# main.net
KiCad netlist of a schematic drawn in EAGLE
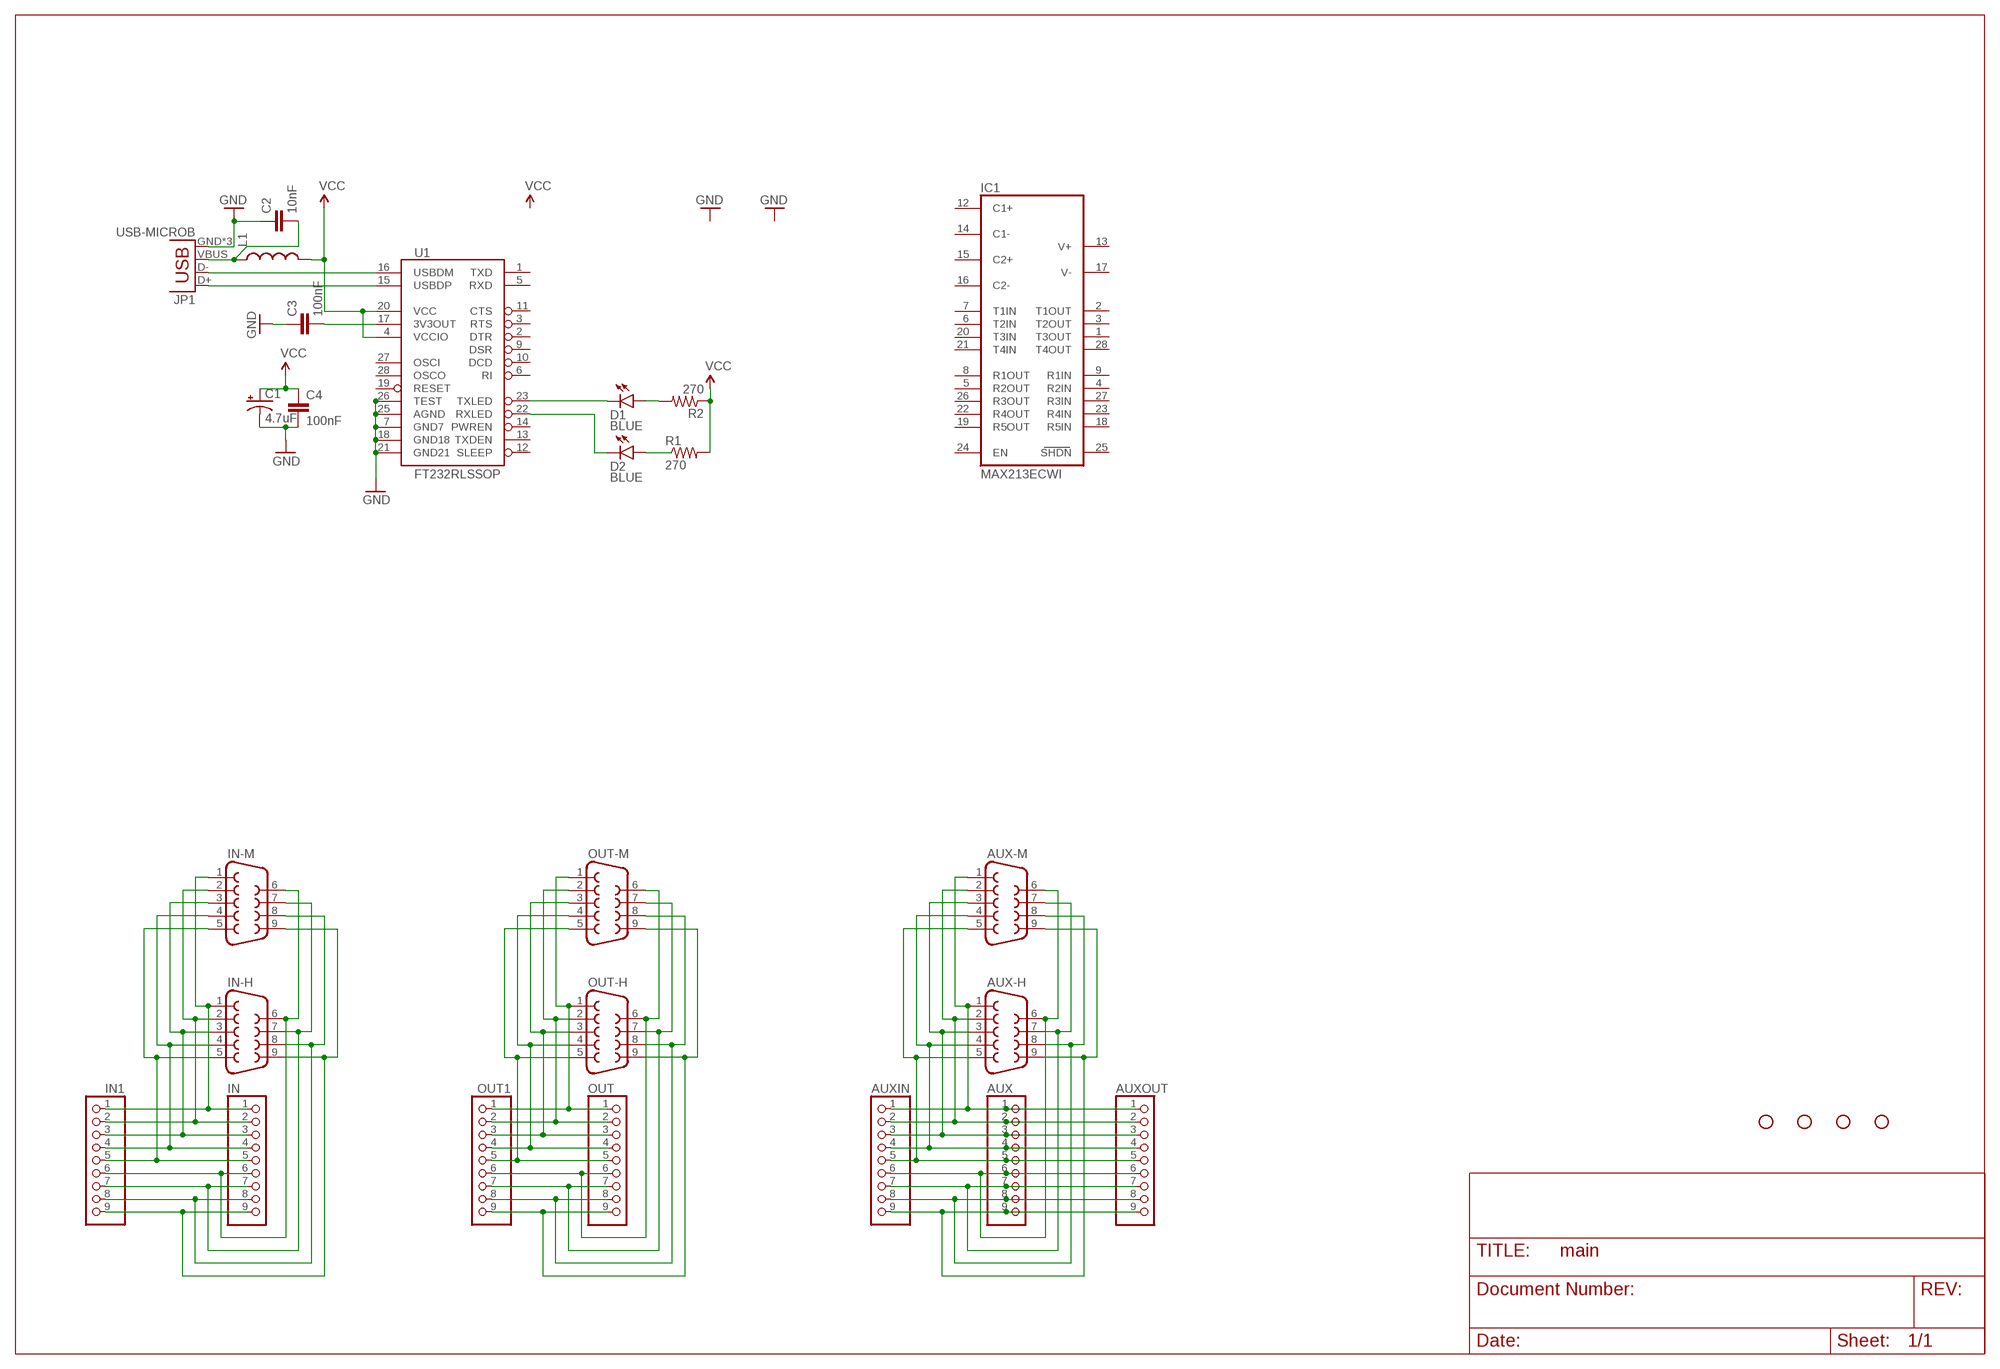
[diagram p0: schematic, sheet 1]

(export (version "E")
  (design (tool "Eeschema 10.0.6"))
  (components
    (comp (ref "AUX")
      (value "PINHD-1X9")
      (footprint "eagle-import:1X09")
      (libsource (lib "eagle-import") (part "PINHD-1X9"))
    )
    (comp (ref "AUX-H")
      (value "F09HP")
      (footprint "eagle-import:F09HP")
      (libsource (lib "eagle-import") (part "F09HP"))
    )
    (comp (ref "AUX-M")
      (value "F09HP")
      (footprint "eagle-import:F09HP")
      (libsource (lib "eagle-import") (part "F09HP"))
    )
    (comp (ref "AUXIN")
      (value "PINHD-1X9")
      (footprint "eagle-import:1X09")
      (libsource (lib "eagle-import") (part "PINHD-1X9"))
    )
    (comp (ref "AUXOUT")
      (value "PINHD-1X9")
      (footprint "eagle-import:1X09")
      (libsource (lib "eagle-import") (part "PINHD-1X9"))
    )
    (comp (ref "C1")
      (value "4.7uF")
      (footprint "eagle-import:EIA3216")
      (libsource (lib "eagle-import") (part "CAP_POL1206"))
    )
    (comp (ref "C2")
      (value "10nF")
      (footprint "eagle-import:0603-CAP")
      (libsource (lib "eagle-import") (part "CAP0603-CAP"))
    )
    (comp (ref "C3")
      (value "100nF")
      (footprint "eagle-import:0603-CAP")
      (libsource (lib "eagle-import") (part "CAP0603-CAP"))
    )
    (comp (ref "C4")
      (value "100nF")
      (footprint "eagle-import:0603-CAP")
      (libsource (lib "eagle-import") (part "CAP0603-CAP"))
    )
    (comp (ref "D1")
      (value "BLUE")
      (footprint "eagle-import:LED-0603")
      (libsource (lib "eagle-import") (part "LED-BLUE0603"))
    )
    (comp (ref "D2")
      (value "BLUE")
      (footprint "eagle-import:LED-0603")
      (libsource (lib "eagle-import") (part "LED-BLUE0603"))
    )
    (comp (ref "IC1")
      (value "MAX213ECWI")
      (footprint "eagle-import:SO28L")
      (fields (field (name "MF") "MAXIM") (field (name "MPN") "MAX213ECWI+"))
      (libsource (lib "eagle-import") (part "MAX213ECWI"))
    )
    (comp (ref "IN")
      (value "PINHD-1X9")
      (footprint "eagle-import:1X09")
      (libsource (lib "eagle-import") (part "PINHD-1X9"))
    )
    (comp (ref "IN-H")
      (value "F09HP")
      (footprint "eagle-import:F09HP")
      (libsource (lib "eagle-import") (part "F09HP"))
    )
    (comp (ref "IN-M")
      (value "F09HP")
      (footprint "eagle-import:F09HP")
      (libsource (lib "eagle-import") (part "F09HP"))
    )
    (comp (ref "IN1")
      (value "PINHD-1X9")
      (footprint "eagle-import:1X09")
      (libsource (lib "eagle-import") (part "PINHD-1X9"))
    )
    (comp (ref "JP1")
      (value "USB-MICROB")
      (footprint "eagle-import:USB-MICROB")
      (libsource (lib "eagle-import") (part "USB-MICROB"))
    )
    (comp (ref "L1")
      (value "INDUCTOR0603")
      (footprint "eagle-import:0603")
      (libsource (lib "eagle-import") (part "INDUCTOR0603"))
    )
    (comp (ref "OUT")
      (value "PINHD-1X9")
      (footprint "eagle-import:1X09")
      (libsource (lib "eagle-import") (part "PINHD-1X9"))
    )
    (comp (ref "OUT-H")
      (value "F09HP")
      (footprint "eagle-import:F09HP")
      (libsource (lib "eagle-import") (part "F09HP"))
    )
    (comp (ref "OUT-M")
      (value "F09HP")
      (footprint "eagle-import:F09HP")
      (libsource (lib "eagle-import") (part "F09HP"))
    )
    (comp (ref "OUT1")
      (value "PINHD-1X9")
      (footprint "eagle-import:1X09")
      (libsource (lib "eagle-import") (part "PINHD-1X9"))
    )
    (comp (ref "R1")
      (value "270")
      (footprint "eagle-import:0603-RES")
      (libsource (lib "eagle-import") (part "RESISTOR0603"))
    )
    (comp (ref "R2")
      (value "270")
      (footprint "eagle-import:0603-RES")
      (libsource (lib "eagle-import") (part "RESISTOR0603"))
    )
    (comp (ref "STANDOFF1")
      (value "STAND-OFF")
      (footprint "eagle-import:STAND-OFF")
      (libsource (lib "eagle-import") (part "STAND-OFF"))
    )
    (comp (ref "STANDOFF2")
      (value "STAND-OFF")
      (footprint "eagle-import:STAND-OFF")
      (libsource (lib "eagle-import") (part "STAND-OFF"))
    )
    (comp (ref "STANDOFF3")
      (value "STAND-OFF")
      (footprint "eagle-import:STAND-OFF")
      (libsource (lib "eagle-import") (part "STAND-OFF"))
    )
    (comp (ref "STANDOFF4")
      (value "STAND-OFF")
      (footprint "eagle-import:STAND-OFF")
      (libsource (lib "eagle-import") (part "STAND-OFF"))
    )
    (comp (ref "U1")
      (value "FT232RLSSOP")
      (footprint "eagle-import:SSOP28DB")
      (libsource (lib "eagle-import") (part "FT232RLSSOP"))
    )
  )
  (nets
    (net (code "1") (name "GND") (class "Default")
      (node (ref "C1") (pin "C") (pinfunction "-_C") (pintype "passive"))
      (node (ref "C2") (pin "1") (pinfunction "1_1") (pintype "passive"))
      (node (ref "C3") (pin "1") (pinfunction "1_1") (pintype "passive"))
      (node (ref "C4") (pin "2") (pinfunction "2_2") (pintype "passive"))
      (node (ref "JP1") (pin "GND") (pinfunction "GND_GND") (pintype "bidirectional"))
      (node (ref "JP1") (pin "MT1") (pinfunction "GND_MT1") (pintype "bidirectional"))
      (node (ref "JP1") (pin "MT2") (pinfunction "GND_MT2") (pintype "bidirectional"))
      (node (ref "U1") (pin "18") (pinfunction "GND18_18") (pintype "power_in"))
      (node (ref "U1") (pin "21") (pinfunction "GND21_21") (pintype "power_in"))
      (node (ref "U1") (pin "25") (pinfunction "AGND_25") (pintype "power_in"))
      (node (ref "U1") (pin "26") (pinfunction "TEST_26") (pintype "input"))
      (node (ref "U1") (pin "7") (pinfunction "GND7_7") (pintype "power_in"))
    )
    (net (code "2") (name "Net-(AUX-H-Pad1)") (class "Default")
      (node (ref "AUX") (pin "1") (pinfunction "1_1") (pintype "passive"))
      (node (ref "AUX-H") (pin "1") (pinfunction "1_1") (pintype "passive"))
      (node (ref "AUX-M") (pin "1") (pinfunction "1_1") (pintype "passive"))
      (node (ref "AUXIN") (pin "1") (pinfunction "1_1") (pintype "passive"))
      (node (ref "AUXOUT") (pin "1") (pinfunction "1_1") (pintype "passive"))
    )
    (net (code "3") (name "Net-(AUX-H-Pad2)") (class "Default")
      (node (ref "AUX") (pin "2") (pinfunction "2_2") (pintype "passive"))
      (node (ref "AUX-H") (pin "2") (pinfunction "2_2") (pintype "passive"))
      (node (ref "AUX-M") (pin "2") (pinfunction "2_2") (pintype "passive"))
      (node (ref "AUXIN") (pin "2") (pinfunction "2_2") (pintype "passive"))
      (node (ref "AUXOUT") (pin "2") (pinfunction "2_2") (pintype "passive"))
    )
    (net (code "4") (name "Net-(AUX-H-Pad3)") (class "Default")
      (node (ref "AUX") (pin "3") (pinfunction "3_3") (pintype "passive"))
      (node (ref "AUX-H") (pin "3") (pinfunction "3_3") (pintype "passive"))
      (node (ref "AUX-M") (pin "3") (pinfunction "3_3") (pintype "passive"))
      (node (ref "AUXIN") (pin "3") (pinfunction "3_3") (pintype "passive"))
      (node (ref "AUXOUT") (pin "3") (pinfunction "3_3") (pintype "passive"))
    )
    (net (code "5") (name "Net-(AUX-H-Pad4)") (class "Default")
      (node (ref "AUX") (pin "4") (pinfunction "4_4") (pintype "passive"))
      (node (ref "AUX-H") (pin "4") (pinfunction "4_4") (pintype "passive"))
      (node (ref "AUX-M") (pin "4") (pinfunction "4_4") (pintype "passive"))
      (node (ref "AUXIN") (pin "4") (pinfunction "4_4") (pintype "passive"))
      (node (ref "AUXOUT") (pin "4") (pinfunction "4_4") (pintype "passive"))
    )
    (net (code "6") (name "Net-(AUX-H-Pad5)") (class "Default")
      (node (ref "AUX") (pin "5") (pinfunction "5_5") (pintype "passive"))
      (node (ref "AUX-H") (pin "5") (pinfunction "5_5") (pintype "passive"))
      (node (ref "AUX-M") (pin "5") (pinfunction "5_5") (pintype "passive"))
      (node (ref "AUXIN") (pin "5") (pinfunction "5_5") (pintype "passive"))
      (node (ref "AUXOUT") (pin "5") (pinfunction "5_5") (pintype "passive"))
    )
    (net (code "7") (name "Net-(AUX-H-Pad6)") (class "Default")
      (node (ref "AUX") (pin "6") (pinfunction "6_6") (pintype "passive"))
      (node (ref "AUX-H") (pin "6") (pinfunction "6_6") (pintype "passive"))
      (node (ref "AUX-M") (pin "6") (pinfunction "6_6") (pintype "passive"))
      (node (ref "AUXIN") (pin "6") (pinfunction "6_6") (pintype "passive"))
      (node (ref "AUXOUT") (pin "6") (pinfunction "6_6") (pintype "passive"))
    )
    (net (code "8") (name "Net-(AUX-H-Pad7)") (class "Default")
      (node (ref "AUX") (pin "7") (pinfunction "7_7") (pintype "passive"))
      (node (ref "AUX-H") (pin "7") (pinfunction "7_7") (pintype "passive"))
      (node (ref "AUX-M") (pin "7") (pinfunction "7_7") (pintype "passive"))
      (node (ref "AUXIN") (pin "7") (pinfunction "7_7") (pintype "passive"))
      (node (ref "AUXOUT") (pin "7") (pinfunction "7_7") (pintype "passive"))
    )
    (net (code "9") (name "Net-(AUX-H-Pad8)") (class "Default")
      (node (ref "AUX") (pin "8") (pinfunction "8_8") (pintype "passive"))
      (node (ref "AUX-H") (pin "8") (pinfunction "8_8") (pintype "passive"))
      (node (ref "AUX-M") (pin "8") (pinfunction "8_8") (pintype "passive"))
      (node (ref "AUXIN") (pin "8") (pinfunction "8_8") (pintype "passive"))
      (node (ref "AUXOUT") (pin "8") (pinfunction "8_8") (pintype "passive"))
    )
    (net (code "10") (name "Net-(AUX-H-Pad9)") (class "Default")
      (node (ref "AUX") (pin "9") (pinfunction "9_9") (pintype "passive"))
      (node (ref "AUX-H") (pin "9") (pinfunction "9_9") (pintype "passive"))
      (node (ref "AUX-M") (pin "9") (pinfunction "9_9") (pintype "passive"))
      (node (ref "AUXIN") (pin "9") (pinfunction "9_9") (pintype "passive"))
      (node (ref "AUXOUT") (pin "9") (pinfunction "9_9") (pintype "passive"))
    )
    (net (code "11") (name "Net-(C2-Pad2)") (class "Default")
      (node (ref "C2") (pin "2") (pinfunction "2_2") (pintype "passive"))
      (node (ref "JP1") (pin "VBUS") (pinfunction "VBUS_VBUS") (pintype "bidirectional"))
      (node (ref "L1") (pin "1") (pinfunction "1_1") (pintype "passive"))
    )
    (net (code "12") (name "Net-(D1-PadA)") (class "Default")
      (node (ref "D1") (pin "A") (pinfunction "A_A") (pintype "passive"))
      (node (ref "R2") (pin "2") (pinfunction "2_2") (pintype "passive"))
    )
    (net (code "13") (name "Net-(IN-H-Pad1)") (class "Default")
      (node (ref "IN") (pin "1") (pinfunction "1_1") (pintype "passive"))
      (node (ref "IN-H") (pin "1") (pinfunction "1_1") (pintype "passive"))
      (node (ref "IN-M") (pin "1") (pinfunction "1_1") (pintype "passive"))
      (node (ref "IN1") (pin "1") (pinfunction "1_1") (pintype "passive"))
    )
    (net (code "14") (name "Net-(IN-H-Pad2)") (class "Default")
      (node (ref "IN") (pin "2") (pinfunction "2_2") (pintype "passive"))
      (node (ref "IN-H") (pin "2") (pinfunction "2_2") (pintype "passive"))
      (node (ref "IN-M") (pin "2") (pinfunction "2_2") (pintype "passive"))
      (node (ref "IN1") (pin "2") (pinfunction "2_2") (pintype "passive"))
    )
    (net (code "15") (name "Net-(IN-H-Pad3)") (class "Default")
      (node (ref "IN") (pin "3") (pinfunction "3_3") (pintype "passive"))
      (node (ref "IN-H") (pin "3") (pinfunction "3_3") (pintype "passive"))
      (node (ref "IN-M") (pin "3") (pinfunction "3_3") (pintype "passive"))
      (node (ref "IN1") (pin "3") (pinfunction "3_3") (pintype "passive"))
    )
    (net (code "16") (name "Net-(IN-H-Pad4)") (class "Default")
      (node (ref "IN") (pin "4") (pinfunction "4_4") (pintype "passive"))
      (node (ref "IN-H") (pin "4") (pinfunction "4_4") (pintype "passive"))
      (node (ref "IN-M") (pin "4") (pinfunction "4_4") (pintype "passive"))
      (node (ref "IN1") (pin "4") (pinfunction "4_4") (pintype "passive"))
    )
    (net (code "17") (name "Net-(IN-H-Pad5)") (class "Default")
      (node (ref "IN") (pin "5") (pinfunction "5_5") (pintype "passive"))
      (node (ref "IN-H") (pin "5") (pinfunction "5_5") (pintype "passive"))
      (node (ref "IN-M") (pin "5") (pinfunction "5_5") (pintype "passive"))
      (node (ref "IN1") (pin "5") (pinfunction "5_5") (pintype "passive"))
    )
    (net (code "18") (name "Net-(IN-H-Pad6)") (class "Default")
      (node (ref "IN") (pin "6") (pinfunction "6_6") (pintype "passive"))
      (node (ref "IN-H") (pin "6") (pinfunction "6_6") (pintype "passive"))
      (node (ref "IN-M") (pin "6") (pinfunction "6_6") (pintype "passive"))
      (node (ref "IN1") (pin "6") (pinfunction "6_6") (pintype "passive"))
    )
    (net (code "19") (name "Net-(IN-H-Pad7)") (class "Default")
      (node (ref "IN") (pin "7") (pinfunction "7_7") (pintype "passive"))
      (node (ref "IN-H") (pin "7") (pinfunction "7_7") (pintype "passive"))
      (node (ref "IN-M") (pin "7") (pinfunction "7_7") (pintype "passive"))
      (node (ref "IN1") (pin "7") (pinfunction "7_7") (pintype "passive"))
    )
    (net (code "20") (name "Net-(IN-H-Pad8)") (class "Default")
      (node (ref "IN") (pin "8") (pinfunction "8_8") (pintype "passive"))
      (node (ref "IN-H") (pin "8") (pinfunction "8_8") (pintype "passive"))
      (node (ref "IN-M") (pin "8") (pinfunction "8_8") (pintype "passive"))
      (node (ref "IN1") (pin "8") (pinfunction "8_8") (pintype "passive"))
    )
    (net (code "21") (name "Net-(IN-H-Pad9)") (class "Default")
      (node (ref "IN") (pin "9") (pinfunction "9_9") (pintype "passive"))
      (node (ref "IN-H") (pin "9") (pinfunction "9_9") (pintype "passive"))
      (node (ref "IN-M") (pin "9") (pinfunction "9_9") (pintype "passive"))
      (node (ref "IN1") (pin "9") (pinfunction "9_9") (pintype "passive"))
    )
    (net (code "22") (name "Net-(OUT-H-Pad1)") (class "Default")
      (node (ref "OUT") (pin "1") (pinfunction "1_1") (pintype "passive"))
      (node (ref "OUT-H") (pin "1") (pinfunction "1_1") (pintype "passive"))
      (node (ref "OUT-M") (pin "1") (pinfunction "1_1") (pintype "passive"))
      (node (ref "OUT1") (pin "1") (pinfunction "1_1") (pintype "passive"))
    )
    (net (code "23") (name "Net-(OUT-H-Pad2)") (class "Default")
      (node (ref "OUT") (pin "2") (pinfunction "2_2") (pintype "passive"))
      (node (ref "OUT-H") (pin "2") (pinfunction "2_2") (pintype "passive"))
      (node (ref "OUT-M") (pin "2") (pinfunction "2_2") (pintype "passive"))
      (node (ref "OUT1") (pin "2") (pinfunction "2_2") (pintype "passive"))
    )
    (net (code "24") (name "Net-(OUT-H-Pad3)") (class "Default")
      (node (ref "OUT") (pin "3") (pinfunction "3_3") (pintype "passive"))
      (node (ref "OUT-H") (pin "3") (pinfunction "3_3") (pintype "passive"))
      (node (ref "OUT-M") (pin "3") (pinfunction "3_3") (pintype "passive"))
      (node (ref "OUT1") (pin "3") (pinfunction "3_3") (pintype "passive"))
    )
    (net (code "25") (name "Net-(OUT-H-Pad4)") (class "Default")
      (node (ref "OUT") (pin "4") (pinfunction "4_4") (pintype "passive"))
      (node (ref "OUT-H") (pin "4") (pinfunction "4_4") (pintype "passive"))
      (node (ref "OUT-M") (pin "4") (pinfunction "4_4") (pintype "passive"))
      (node (ref "OUT1") (pin "4") (pinfunction "4_4") (pintype "passive"))
    )
    (net (code "26") (name "Net-(OUT-H-Pad5)") (class "Default")
      (node (ref "OUT") (pin "5") (pinfunction "5_5") (pintype "passive"))
      (node (ref "OUT-H") (pin "5") (pinfunction "5_5") (pintype "passive"))
      (node (ref "OUT-M") (pin "5") (pinfunction "5_5") (pintype "passive"))
      (node (ref "OUT1") (pin "5") (pinfunction "5_5") (pintype "passive"))
    )
    (net (code "27") (name "Net-(OUT-H-Pad6)") (class "Default")
      (node (ref "OUT") (pin "6") (pinfunction "6_6") (pintype "passive"))
      (node (ref "OUT-H") (pin "6") (pinfunction "6_6") (pintype "passive"))
      (node (ref "OUT-M") (pin "6") (pinfunction "6_6") (pintype "passive"))
      (node (ref "OUT1") (pin "6") (pinfunction "6_6") (pintype "passive"))
    )
    (net (code "28") (name "Net-(OUT-H-Pad7)") (class "Default")
      (node (ref "OUT") (pin "7") (pinfunction "7_7") (pintype "passive"))
      (node (ref "OUT-H") (pin "7") (pinfunction "7_7") (pintype "passive"))
      (node (ref "OUT-M") (pin "7") (pinfunction "7_7") (pintype "passive"))
      (node (ref "OUT1") (pin "7") (pinfunction "7_7") (pintype "passive"))
    )
    (net (code "29") (name "Net-(OUT-H-Pad8)") (class "Default")
      (node (ref "OUT") (pin "8") (pinfunction "8_8") (pintype "passive"))
      (node (ref "OUT-H") (pin "8") (pinfunction "8_8") (pintype "passive"))
      (node (ref "OUT-M") (pin "8") (pinfunction "8_8") (pintype "passive"))
      (node (ref "OUT1") (pin "8") (pinfunction "8_8") (pintype "passive"))
    )
    (net (code "30") (name "Net-(OUT-H-Pad9)") (class "Default")
      (node (ref "OUT") (pin "9") (pinfunction "9_9") (pintype "passive"))
      (node (ref "OUT-H") (pin "9") (pinfunction "9_9") (pintype "passive"))
      (node (ref "OUT-M") (pin "9") (pinfunction "9_9") (pintype "passive"))
      (node (ref "OUT1") (pin "9") (pinfunction "9_9") (pintype "passive"))
    )
    (net (code "31") (name "Net-(U1-3V3OUT)") (class "Default")
      (node (ref "C3") (pin "2") (pinfunction "2_2") (pintype "passive"))
      (node (ref "U1") (pin "17") (pinfunction "3V3OUT_17") (pintype "output"))
    )
    (net (code "32") (name "Net-(U1-RXLED)") (class "Default")
      (node (ref "D2") (pin "C") (pinfunction "C_C") (pintype "passive"))
      (node (ref "U1") (pin "22") (pinfunction "RXLED_22") (pintype "input"))
    )
    (net (code "33") (name "Net-(U1-TXLED)") (class "Default")
      (node (ref "D1") (pin "C") (pinfunction "C_C") (pintype "passive"))
      (node (ref "U1") (pin "23") (pinfunction "TXLED_23") (pintype "input"))
    )
    (net (code "34") (name "Net-(U1-USBDM)") (class "Default")
      (node (ref "JP1") (pin "D-") (pinfunction "D-_D-") (pintype "bidirectional"))
      (node (ref "U1") (pin "16") (pinfunction "USBDM_16") (pintype "bidirectional"))
    )
    (net (code "35") (name "Net-(U1-USBDP)") (class "Default")
      (node (ref "JP1") (pin "D+") (pinfunction "D+_D+") (pintype "bidirectional"))
      (node (ref "U1") (pin "15") (pinfunction "USBDP_15") (pintype "bidirectional"))
    )
    (net (code "36") (name "VCC") (class "Default")
      (node (ref "C1") (pin "A") (pinfunction "+_A") (pintype "passive"))
      (node (ref "C4") (pin "1") (pinfunction "1_1") (pintype "passive"))
      (node (ref "L1") (pin "2") (pinfunction "2_2") (pintype "passive"))
      (node (ref "R1") (pin "2") (pinfunction "2_2") (pintype "passive"))
      (node (ref "R2") (pin "1") (pinfunction "1_1") (pintype "passive"))
      (node (ref "U1") (pin "20") (pinfunction "VCC_20") (pintype "power_in"))
      (node (ref "U1") (pin "4") (pinfunction "VCCIO_4") (pintype "power_in"))
    )
    (net (code "37") (name "unconnected-(D2-PadA)") (class "Default")
      (node (ref "D2") (pin "A") (pinfunction "A_A") (pintype "passive"))
    )
    (net (code "38") (name "unconnected-(IC1A-C1+-Pad12)") (class "Default")
      (node (ref "IC1") (pin "12") (pinfunction "C1+_12") (pintype "passive"))
    )
    (net (code "39") (name "unconnected-(IC1A-C1--Pad14)") (class "Default")
      (node (ref "IC1") (pin "14") (pinfunction "C1-_14") (pintype "passive"))
    )
    (net (code "40") (name "unconnected-(IC1A-C2+-Pad15)") (class "Default")
      (node (ref "IC1") (pin "15") (pinfunction "C2+_15") (pintype "passive"))
    )
    (net (code "41") (name "unconnected-(IC1A-C2--Pad16)") (class "Default")
      (node (ref "IC1") (pin "16") (pinfunction "C2-_16") (pintype "passive"))
    )
    (net (code "42") (name "unconnected-(IC1A-EN-Pad24)") (class "Default")
      (node (ref "IC1") (pin "24") (pinfunction "EN_24") (pintype "input"))
    )
    (net (code "43") (name "unconnected-(IC1A-R1IN-Pad9)") (class "Default")
      (node (ref "IC1") (pin "9") (pinfunction "R1IN_9") (pintype "input"))
    )
    (net (code "44") (name "unconnected-(IC1A-R1OUT-Pad8)") (class "Default")
      (node (ref "IC1") (pin "8") (pinfunction "R1OUT_8") (pintype "output"))
    )
    (net (code "45") (name "unconnected-(IC1A-R2IN-Pad4)") (class "Default")
      (node (ref "IC1") (pin "4") (pinfunction "R2IN_4") (pintype "input"))
    )
    (net (code "46") (name "unconnected-(IC1A-R2OUT-Pad5)") (class "Default")
      (node (ref "IC1") (pin "5") (pinfunction "R2OUT_5") (pintype "output"))
    )
    (net (code "47") (name "unconnected-(IC1A-R3IN-Pad27)") (class "Default")
      (node (ref "IC1") (pin "27") (pinfunction "R3IN_27") (pintype "input"))
    )
    (net (code "48") (name "unconnected-(IC1A-R3OUT-Pad26)") (class "Default")
      (node (ref "IC1") (pin "26") (pinfunction "R3OUT_26") (pintype "output"))
    )
    (net (code "49") (name "unconnected-(IC1A-R4IN-Pad23)") (class "Default")
      (node (ref "IC1") (pin "23") (pinfunction "R4IN_23") (pintype "input"))
    )
    (net (code "50") (name "unconnected-(IC1A-R4OUT-Pad22)") (class "Default")
      (node (ref "IC1") (pin "22") (pinfunction "R4OUT_22") (pintype "output"))
    )
    (net (code "51") (name "unconnected-(IC1A-R5IN-Pad18)") (class "Default")
      (node (ref "IC1") (pin "18") (pinfunction "R5IN_18") (pintype "input"))
    )
    (net (code "52") (name "unconnected-(IC1A-R5OUT-Pad19)") (class "Default")
      (node (ref "IC1") (pin "19") (pinfunction "R5OUT_19") (pintype "output"))
    )
    (net (code "53") (name "unconnected-(IC1A-SHDN-Pad25)") (class "Default")
      (node (ref "IC1") (pin "25") (pinfunction "SHDN_25") (pintype "input"))
    )
    (net (code "54") (name "unconnected-(IC1A-T1IN-Pad7)") (class "Default")
      (node (ref "IC1") (pin "7") (pinfunction "T1IN_7") (pintype "input"))
    )
    (net (code "55") (name "unconnected-(IC1A-T1OUT-Pad2)") (class "Default")
      (node (ref "IC1") (pin "2") (pinfunction "T1OUT_2") (pintype "output"))
    )
    (net (code "56") (name "unconnected-(IC1A-T2IN-Pad6)") (class "Default")
      (node (ref "IC1") (pin "6") (pinfunction "T2IN_6") (pintype "input"))
    )
    (net (code "57") (name "unconnected-(IC1A-T2OUT-Pad3)") (class "Default")
      (node (ref "IC1") (pin "3") (pinfunction "T2OUT_3") (pintype "output"))
    )
    (net (code "58") (name "unconnected-(IC1A-T3IN-Pad20)") (class "Default")
      (node (ref "IC1") (pin "20") (pinfunction "T3IN_20") (pintype "input"))
    )
    (net (code "59") (name "unconnected-(IC1A-T3OUT-Pad1)") (class "Default")
      (node (ref "IC1") (pin "1") (pinfunction "T3OUT_1") (pintype "output"))
    )
    (net (code "60") (name "unconnected-(IC1A-T4IN-Pad21)") (class "Default")
      (node (ref "IC1") (pin "21") (pinfunction "T4IN_21") (pintype "input"))
    )
    (net (code "61") (name "unconnected-(IC1A-T4OUT-Pad28)") (class "Default")
      (node (ref "IC1") (pin "28") (pinfunction "T4OUT_28") (pintype "output"))
    )
    (net (code "62") (name "unconnected-(IC1A-V+-Pad13)") (class "Default")
      (node (ref "IC1") (pin "13") (pinfunction "V+_13") (pintype "passive"))
    )
    (net (code "63") (name "unconnected-(IC1A-V--Pad17)") (class "Default")
      (node (ref "IC1") (pin "17") (pinfunction "V-_17") (pintype "passive"))
    )
    (net (code "64") (name "unconnected-(R1-Pad1)") (class "Default")
      (node (ref "R1") (pin "1") (pinfunction "1_1") (pintype "passive"))
    )
    (net (code "65") (name "unconnected-(U1-CTS-Pad11)") (class "Default")
      (node (ref "U1") (pin "11") (pinfunction "CTS_11") (pintype "input"))
    )
    (net (code "66") (name "unconnected-(U1-DCD-Pad10)") (class "Default")
      (node (ref "U1") (pin "10") (pinfunction "DCD_10") (pintype "input"))
    )
    (net (code "67") (name "unconnected-(U1-DSR-Pad9)") (class "Default")
      (node (ref "U1") (pin "9") (pinfunction "DSR_9") (pintype "input"))
    )
    (net (code "68") (name "unconnected-(U1-DTR-Pad2)") (class "Default")
      (node (ref "U1") (pin "2") (pinfunction "DTR_2") (pintype "output"))
    )
    (net (code "69") (name "unconnected-(U1-OSCI-Pad27)") (class "Default")
      (node (ref "U1") (pin "27") (pinfunction "OSCI_27") (pintype "input"))
    )
    (net (code "70") (name "unconnected-(U1-OSCO-Pad28)") (class "Default")
      (node (ref "U1") (pin "28") (pinfunction "OSCO_28") (pintype "output"))
    )
    (net (code "71") (name "unconnected-(U1-PWREN-Pad14)") (class "Default")
      (node (ref "U1") (pin "14") (pinfunction "PWREN_14") (pintype "input"))
    )
    (net (code "72") (name "unconnected-(U1-RESET-Pad19)") (class "Default")
      (node (ref "U1") (pin "19") (pinfunction "RESET_19") (pintype "input"))
    )
    (net (code "73") (name "unconnected-(U1-RI-Pad6)") (class "Default")
      (node (ref "U1") (pin "6") (pinfunction "RI_6") (pintype "input"))
    )
    (net (code "74") (name "unconnected-(U1-RTS-Pad3)") (class "Default")
      (node (ref "U1") (pin "3") (pinfunction "RTS_3") (pintype "output"))
    )
    (net (code "75") (name "unconnected-(U1-RXD-Pad5)") (class "Default")
      (node (ref "U1") (pin "5") (pinfunction "RXD_5") (pintype "input"))
    )
    (net (code "76") (name "unconnected-(U1-SLEEP-Pad12)") (class "Default")
      (node (ref "U1") (pin "12") (pinfunction "SLEEP_12") (pintype "input"))
    )
    (net (code "77") (name "unconnected-(U1-TXD-Pad1)") (class "Default")
      (node (ref "U1") (pin "1") (pinfunction "TXD_1") (pintype "output"))
    )
    (net (code "78") (name "unconnected-(U1-TXDEN-Pad13)") (class "Default")
      (node (ref "U1") (pin "13") (pinfunction "TXDEN_13") (pintype "input"))
    )
  )
)
